# Raspi_Photometer.net
KiCad netlist of a schematic drawn in EAGLE
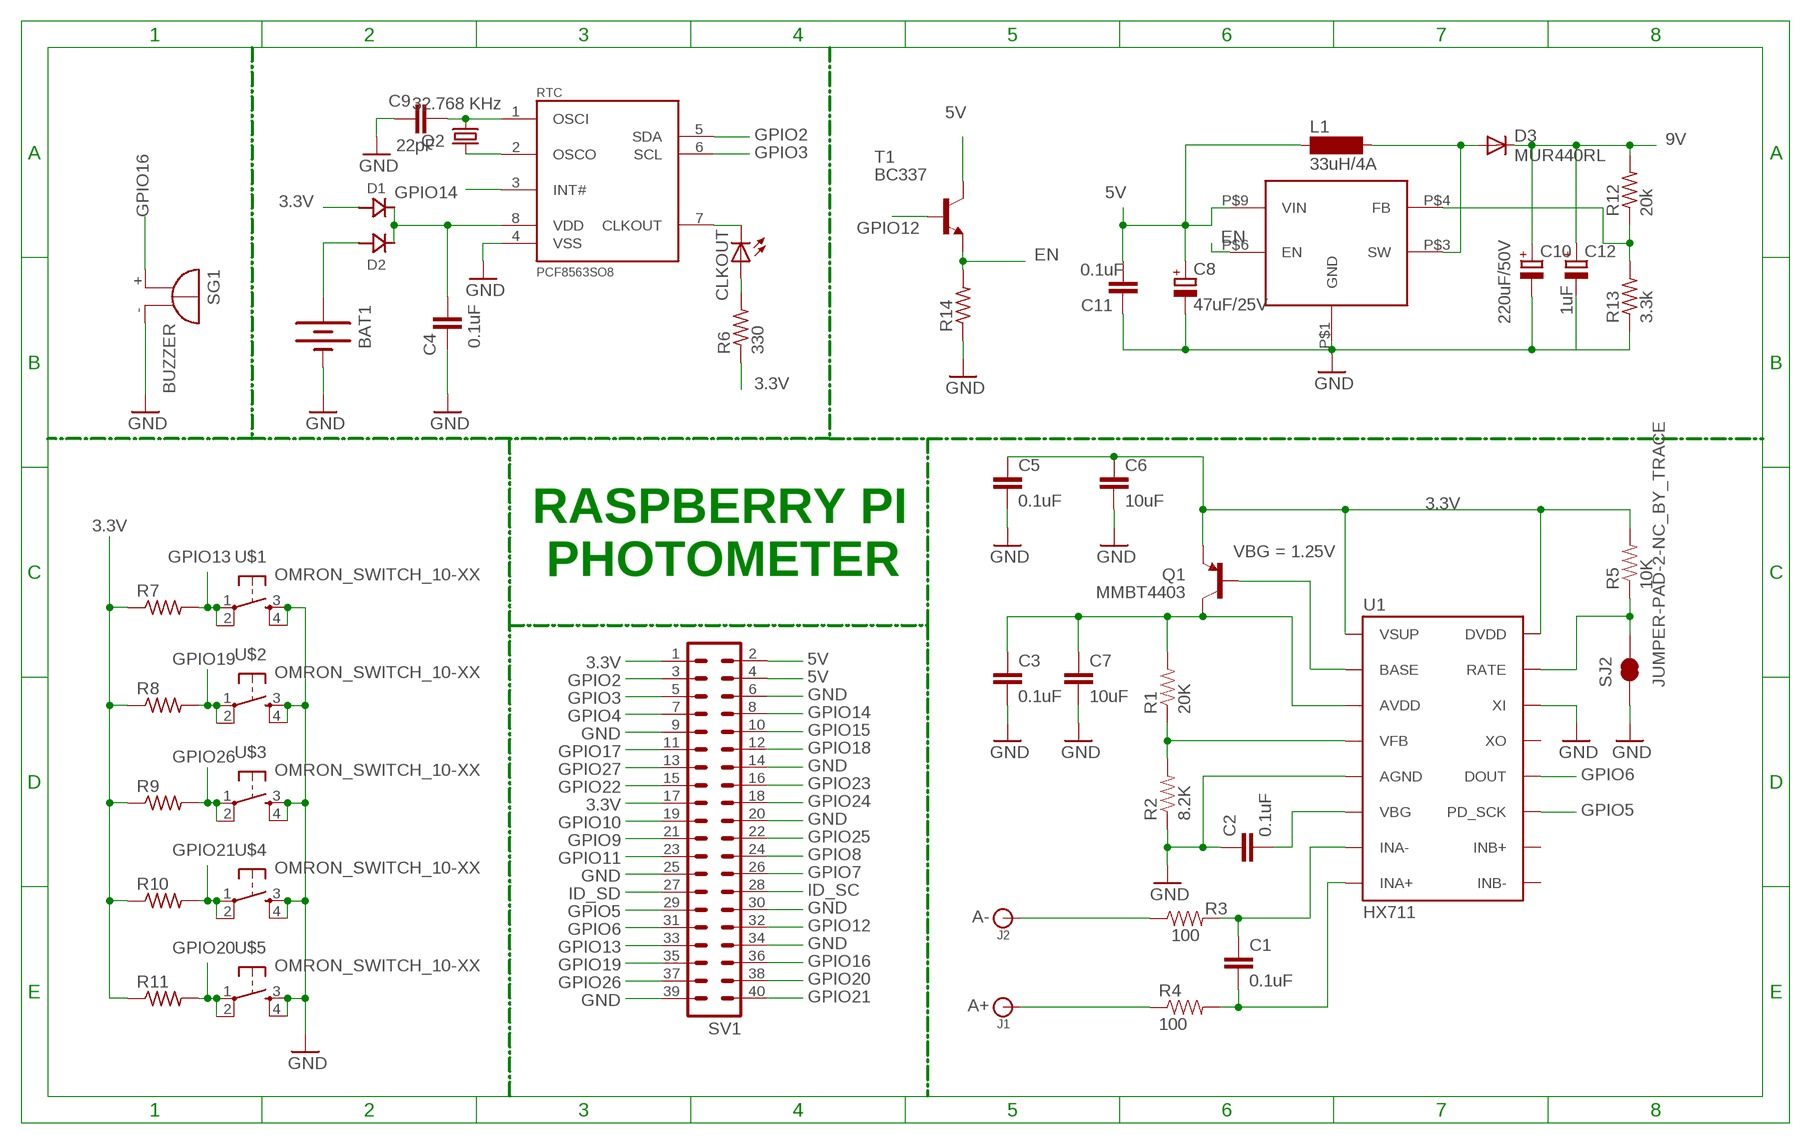
[diagram p0: schematic, sheet 1]

(export (version "E")
  (design (tool "Eeschema 10.0.6"))
  (components
    (comp (ref "BAT1")
      (value "BATTERY20PTH")
      (footprint "eagle-import:BATTCOM_20MM_PTH")
      (libsource (lib "eagle-import") (part "BATTERY20PTH"))
    )
    (comp (ref "C1")
      (value "0.1uF")
      (footprint "eagle-import:0603-CAP")
      (libsource (lib "eagle-import") (part "0.1UF-25V-5%(0603)"))
    )
    (comp (ref "C2")
      (value "0.1uF")
      (footprint "eagle-import:0603-CAP")
      (libsource (lib "eagle-import") (part "0.1UF-25V-5%(0603)"))
    )
    (comp (ref "C3")
      (value "0.1uF")
      (footprint "eagle-import:0603-CAP")
      (libsource (lib "eagle-import") (part "0.1UF-25V-5%(0603)"))
    )
    (comp (ref "C4")
      (value "0.1uF")
      (footprint "eagle-import:C0805K")
      (libsource (lib "eagle-import") (part "C-EUC0805K"))
    )
    (comp (ref "C5")
      (value "0.1uF")
      (footprint "eagle-import:0603-CAP")
      (libsource (lib "eagle-import") (part "0.1UF-25V-5%(0603)"))
    )
    (comp (ref "C6")
      (value "10uF")
      (footprint "eagle-import:1210")
      (libsource (lib "eagle-import") (part "10UF50V20%(1210)"))
    )
    (comp (ref "C7")
      (value "10uF")
      (footprint "eagle-import:1210")
      (libsource (lib "eagle-import") (part "10UF50V20%(1210)"))
    )
    (comp (ref "C8")
      (value "47uF/25V")
      (footprint "eagle-import:E3,5-10")
      (libsource (lib "eagle-import") (part "CPOL-EUE3.5-10"))
    )
    (comp (ref "C9")
      (value "22pF")
      (footprint "eagle-import:C0805K")
      (libsource (lib "eagle-import") (part "C-EUC0805K"))
    )
    (comp (ref "C10")
      (value "220uF/50V")
      (footprint "eagle-import:E5-10,5")
      (libsource (lib "eagle-import") (part "CPOL-EUE5-10.5"))
    )
    (comp (ref "C11")
      (value "0.1uF")
      (footprint "eagle-import:C0603")
      (libsource (lib "eagle-import") (part "C-EUC0603"))
    )
    (comp (ref "C12")
      (value "1uF")
      (footprint "eagle-import:E2,5-5")
      (libsource (lib "eagle-import") (part "rcl (2)_CPOL-EUE2.5-5"))
    )
    (comp (ref "CLKOUT")
      (value "LED0805")
      (footprint "eagle-import:CHIPLED_0805")
      (libsource (lib "eagle-import") (part "LED0805"))
    )
    (comp (ref "D1")
      (value "SS14")
      (footprint "eagle-import:DO214")
      (libsource (lib "eagle-import") (part "SS14"))
    )
    (comp (ref "D2")
      (value "SS14")
      (footprint "eagle-import:DO214")
      (libsource (lib "eagle-import") (part "SS14"))
    )
    (comp (ref "D3")
      (value "MUR440RL")
      (footprint "eagle-import:C2673")
      (libsource (lib "eagle-import") (part "MUR440RL"))
    )
    (comp (ref "J1")
      (value "BANANA_CONN")
      (footprint "eagle-import:BANANA_CONN")
      (libsource (lib "eagle-import") (part "BANANA_CONN"))
    )
    (comp (ref "J2")
      (value "BANANA_CONN")
      (footprint "eagle-import:BANANA_CONN")
      (libsource (lib "eagle-import") (part "BANANA_CONN"))
    )
    (comp (ref "L1")
      (value "33uH/4A")
      (footprint "eagle-import:MS85")
      (libsource (lib "eagle-import") (part "MS85"))
    )
    (comp (ref "Q1")
      (value "MMBT4403")
      (footprint "eagle-import:SOT23-3")
      (libsource (lib "eagle-import") (part "TRANSISTOR_PNPMMBT4403"))
    )
    (comp (ref "Q2")
      (value "32.768 KHz")
      (footprint "eagle-import:TC26H")
      (libsource (lib "eagle-import") (part "CRYSTALTC26H"))
    )
    (comp (ref "R1")
      (value "20K")
      (footprint "eagle-import:0603-RES")
      (libsource (lib "eagle-import") (part "20KOHM1/10W1%(0603)"))
    )
    (comp (ref "R2")
      (value "8.2K")
      (footprint "eagle-import:0603-RES")
      (libsource (lib "eagle-import") (part "8.2KOHM-1/10W-5%(0603)"))
    )
    (comp (ref "R3")
      (value "100")
      (footprint "eagle-import:0603-RES")
      (libsource (lib "eagle-import") (part "100OHM-1/10W-1%(0603)"))
    )
    (comp (ref "R4")
      (value "100")
      (footprint "eagle-import:0603-RES")
      (libsource (lib "eagle-import") (part "100OHM-1/10W-1%(0603)"))
    )
    (comp (ref "R5")
      (value "10K")
      (footprint "eagle-import:0603-RES")
      (libsource (lib "eagle-import") (part "10KOHM-1/10W-1%(0603)0603"))
    )
    (comp (ref "R6")
      (value "330")
      (footprint "eagle-import:0204_7")
      (libsource (lib "eagle-import") (part "R-US_0204/7"))
    )
    (comp (ref "R7")
      (value "R-US_0204/7")
      (footprint "eagle-import:0204_7")
      (libsource (lib "eagle-import") (part "R-US_0204/7"))
    )
    (comp (ref "R8")
      (value "R-US_0204/7")
      (footprint "eagle-import:0204_7")
      (libsource (lib "eagle-import") (part "R-US_0204/7"))
    )
    (comp (ref "R9")
      (value "R-US_0204/7")
      (footprint "eagle-import:0204_7")
      (libsource (lib "eagle-import") (part "R-US_0204/7"))
    )
    (comp (ref "R10")
      (value "R-US_0204/7")
      (footprint "eagle-import:0204_7")
      (libsource (lib "eagle-import") (part "R-US_0204/7"))
    )
    (comp (ref "R11")
      (value "R-US_0204/7")
      (footprint "eagle-import:0204_7")
      (libsource (lib "eagle-import") (part "R-US_0204/7"))
    )
    (comp (ref "R12")
      (value "20k")
      (footprint "eagle-import:0207_7")
      (libsource (lib "eagle-import") (part "RESISTOR0207/7"))
    )
    (comp (ref "R13")
      (value "3.3k")
      (footprint "eagle-import:0207_7")
      (libsource (lib "eagle-import") (part "RESISTOR0207/7"))
    )
    (comp (ref "R14")
      (value "R-US_0207/10")
      (footprint "eagle-import:0207_10")
      (libsource (lib "eagle-import") (part "R-US_0207/10"))
    )
    (comp (ref "RTC")
      (value "PCF8563SO8")
      (footprint "eagle-import:SOIC8")
      (libsource (lib "eagle-import") (part "PCF8563SO8"))
    )
    (comp (ref "SG1")
      (value "BUZZER")
      (footprint "eagle-import:F_TMB")
      (libsource (lib "eagle-import") (part "BUZZER"))
    )
    (comp (ref "SJ2")
      (value "JUMPER-PAD-2-NC_BY_TRACE")
      (footprint "eagle-import:PAD-JUMPER-2-NC_BY_TRACE_YES_SILK")
      (libsource (lib "eagle-import") (part "JUMPER-PAD-2-NC_BY_TRACE"))
    )
    (comp (ref "SV1")
      (value "ML40")
      (footprint "eagle-import:ML40")
      (libsource (lib "eagle-import") (part "ML40"))
    )
    (comp (ref "T1")
      (value "BC337")
      (footprint "eagle-import:TO92")
      (libsource (lib "eagle-import") (part "BC337"))
    )
    (comp (ref "U$1")
      (value "OMRON_SWITCH_10-XX")
      (footprint "eagle-import:B3F-10XX")
      (libsource (lib "eagle-import") (part "OMRON_SWITCH_10-XX"))
    )
    (comp (ref "U$2")
      (value "OMRON_SWITCH_10-XX")
      (footprint "eagle-import:B3F-10XX")
      (libsource (lib "eagle-import") (part "OMRON_SWITCH_10-XX"))
    )
    (comp (ref "U$3")
      (value "OMRON_SWITCH_10-XX")
      (footprint "eagle-import:B3F-10XX")
      (libsource (lib "eagle-import") (part "OMRON_SWITCH_10-XX"))
    )
    (comp (ref "U$4")
      (value "OMRON_SWITCH_10-XX")
      (footprint "eagle-import:B3F-10XX")
      (libsource (lib "eagle-import") (part "OMRON_SWITCH_10-XX"))
    )
    (comp (ref "U$5")
      (value "OMRON_SWITCH_10-XX")
      (footprint "eagle-import:B3F-10XX")
      (libsource (lib "eagle-import") (part "OMRON_SWITCH_10-XX"))
    )
    (comp (ref "U$6")
      (value "XL6009")
      (footprint "eagle-import:TO-263-5L")
      (libsource (lib "eagle-import") (part "XL6009"))
    )
    (comp (ref "U1")
      (value "HX711")
      (footprint "eagle-import:SO16")
      (libsource (lib "eagle-import") (part "HX711HX711"))
    )
  )
  (nets
    (net (code "1") (name "/3.3V") (class "Default")
      (node (ref "C5") (pin "1") (pinfunction "1_1") (pintype "passive"))
      (node (ref "C6") (pin "1") (pinfunction "1_1") (pintype "passive"))
      (node (ref "D1") (pin "ANODE") (pinfunction "ANODE_ANODE") (pintype "bidirectional"))
      (node (ref "Q1") (pin "2") (pinfunction "E_2") (pintype "passive"))
      (node (ref "R10") (pin "1") (pinfunction "1_1") (pintype "passive"))
      (node (ref "R11") (pin "1") (pinfunction "1_1") (pintype "passive"))
      (node (ref "R5") (pin "2") (pinfunction "2_2") (pintype "passive"))
      (node (ref "R6") (pin "1") (pinfunction "1_1") (pintype "passive"))
      (node (ref "R7") (pin "1") (pinfunction "1_1") (pintype "passive"))
      (node (ref "R8") (pin "1") (pinfunction "1_1") (pintype "passive"))
      (node (ref "R9") (pin "1") (pinfunction "1_1") (pintype "passive"))
      (node (ref "SV1") (pin "1") (pinfunction "1_1") (pintype "passive"))
      (node (ref "SV1") (pin "17") (pinfunction "17_17") (pintype "passive"))
      (node (ref "U1") (pin "1") (pinfunction "VSUP_1") (pintype "bidirectional"))
      (node (ref "U1") (pin "16") (pinfunction "DVDD_16") (pintype "bidirectional"))
    )
    (net (code "2") (name "/5V") (class "Default")
      (node (ref "C11") (pin "2") (pinfunction "2_2") (pintype "passive"))
      (node (ref "C8") (pin "+") (pinfunction "+_+") (pintype "passive"))
      (node (ref "L1") (pin "1") (pinfunction "1_1") (pintype "passive"))
      (node (ref "SV1") (pin "2") (pinfunction "2_2") (pintype "passive"))
      (node (ref "SV1") (pin "4") (pinfunction "4_4") (pintype "passive"))
      (node (ref "T1") (pin "3") (pinfunction "C_3") (pintype "passive"))
      (node (ref "U$6") (pin "P$9") (pinfunction "VIN_P$9") (pintype "bidirectional"))
    )
    (net (code "3") (name "/9V") (class "Default")
      (node (ref "C10") (pin "+") (pinfunction "+_+") (pintype "passive"))
      (node (ref "C12") (pin "+") (pinfunction "+_+") (pintype "passive"))
      (node (ref "D3") (pin "C") (pinfunction "C_C") (pintype "passive"))
      (node (ref "R12") (pin "2") (pinfunction "2_2") (pintype "passive"))
    )
    (net (code "4") (name "/A+") (class "Default")
      (node (ref "J1") (pin "P$2") (pinfunction "1_P$2") (pintype "passive"))
      (node (ref "R4") (pin "1") (pinfunction "1_1") (pintype "passive"))
    )
    (net (code "5") (name "/A-") (class "Default")
      (node (ref "J2") (pin "P$2") (pinfunction "1_P$2") (pintype "passive"))
      (node (ref "R3") (pin "1") (pinfunction "1_1") (pintype "passive"))
    )
    (net (code "6") (name "/EN") (class "Default")
      (node (ref "R14") (pin "2") (pinfunction "2_2") (pintype "passive"))
      (node (ref "T1") (pin "1") (pinfunction "E_1") (pintype "passive"))
      (node (ref "U$6") (pin "P$6") (pinfunction "EN_P$6") (pintype "bidirectional"))
    )
    (net (code "7") (name "/GPIO2") (class "Default")
      (node (ref "RTC") (pin "5") (pinfunction "SDA_5") (pintype "bidirectional"))
      (node (ref "SV1") (pin "3") (pinfunction "3_3") (pintype "passive"))
    )
    (net (code "8") (name "/GPIO3") (class "Default")
      (node (ref "RTC") (pin "6") (pinfunction "SCL_6") (pintype "bidirectional"))
      (node (ref "SV1") (pin "5") (pinfunction "5_5") (pintype "passive"))
    )
    (net (code "9") (name "/GPIO4") (class "Default")
      (node (ref "SV1") (pin "7") (pinfunction "7_7") (pintype "passive"))
    )
    (net (code "10") (name "/GPIO5") (class "Default")
      (node (ref "SV1") (pin "29") (pinfunction "29_29") (pintype "passive"))
      (node (ref "U1") (pin "11") (pinfunction "PD_SCK_11") (pintype "bidirectional"))
    )
    (net (code "11") (name "/GPIO6") (class "Default")
      (node (ref "SV1") (pin "31") (pinfunction "31_31") (pintype "passive"))
      (node (ref "U1") (pin "12") (pinfunction "DOUT_12") (pintype "bidirectional"))
    )
    (net (code "12") (name "/GPIO7") (class "Default")
      (node (ref "SV1") (pin "26") (pinfunction "26_26") (pintype "passive"))
    )
    (net (code "13") (name "/GPIO8") (class "Default")
      (node (ref "SV1") (pin "24") (pinfunction "24_24") (pintype "passive"))
    )
    (net (code "14") (name "/GPIO9") (class "Default")
      (node (ref "SV1") (pin "21") (pinfunction "21_21") (pintype "passive"))
    )
    (net (code "15") (name "/GPIO10") (class "Default")
      (node (ref "SV1") (pin "19") (pinfunction "19_19") (pintype "passive"))
    )
    (net (code "16") (name "/GPIO11") (class "Default")
      (node (ref "SV1") (pin "23") (pinfunction "23_23") (pintype "passive"))
    )
    (net (code "17") (name "/GPIO12") (class "Default")
      (node (ref "SV1") (pin "32") (pinfunction "32_32") (pintype "passive"))
      (node (ref "T1") (pin "2") (pinfunction "B_2") (pintype "passive"))
    )
    (net (code "18") (name "/GPIO13") (class "Default")
      (node (ref "R7") (pin "2") (pinfunction "2_2") (pintype "passive"))
      (node (ref "SV1") (pin "33") (pinfunction "33_33") (pintype "passive"))
      (node (ref "U$1") (pin "1") (pinfunction "P_1") (pintype "passive"))
      (node (ref "U$1") (pin "2") (pinfunction "P1_2") (pintype "passive"))
    )
    (net (code "19") (name "/GPIO14") (class "Default")
      (node (ref "RTC") (pin "3") (pinfunction "INT#_3") (pintype "bidirectional"))
      (node (ref "SV1") (pin "8") (pinfunction "8_8") (pintype "passive"))
    )
    (net (code "20") (name "/GPIO15") (class "Default")
      (node (ref "SV1") (pin "10") (pinfunction "10_10") (pintype "passive"))
    )
    (net (code "21") (name "/GPIO16") (class "Default")
      (node (ref "SG1") (pin "+") (pinfunction "+_+") (pintype "passive"))
      (node (ref "SV1") (pin "36") (pinfunction "36_36") (pintype "passive"))
    )
    (net (code "22") (name "/GPIO17") (class "Default")
      (node (ref "SV1") (pin "11") (pinfunction "11_11") (pintype "passive"))
    )
    (net (code "23") (name "/GPIO18") (class "Default")
      (node (ref "SV1") (pin "12") (pinfunction "12_12") (pintype "passive"))
    )
    (net (code "24") (name "/GPIO19") (class "Default")
      (node (ref "R8") (pin "2") (pinfunction "2_2") (pintype "passive"))
      (node (ref "SV1") (pin "35") (pinfunction "35_35") (pintype "passive"))
      (node (ref "U$2") (pin "1") (pinfunction "P_1") (pintype "passive"))
      (node (ref "U$2") (pin "2") (pinfunction "P1_2") (pintype "passive"))
    )
    (net (code "25") (name "/GPIO20") (class "Default")
      (node (ref "R11") (pin "2") (pinfunction "2_2") (pintype "passive"))
      (node (ref "SV1") (pin "38") (pinfunction "38_38") (pintype "passive"))
      (node (ref "U$5") (pin "1") (pinfunction "P_1") (pintype "passive"))
      (node (ref "U$5") (pin "2") (pinfunction "P1_2") (pintype "passive"))
    )
    (net (code "26") (name "/GPIO21") (class "Default")
      (node (ref "R10") (pin "2") (pinfunction "2_2") (pintype "passive"))
      (node (ref "SV1") (pin "40") (pinfunction "40_40") (pintype "passive"))
      (node (ref "U$4") (pin "1") (pinfunction "P_1") (pintype "passive"))
      (node (ref "U$4") (pin "2") (pinfunction "P1_2") (pintype "passive"))
    )
    (net (code "27") (name "/GPIO22") (class "Default")
      (node (ref "SV1") (pin "15") (pinfunction "15_15") (pintype "passive"))
    )
    (net (code "28") (name "/GPIO23") (class "Default")
      (node (ref "SV1") (pin "16") (pinfunction "16_16") (pintype "passive"))
    )
    (net (code "29") (name "/GPIO24") (class "Default")
      (node (ref "SV1") (pin "18") (pinfunction "18_18") (pintype "passive"))
    )
    (net (code "30") (name "/GPIO25") (class "Default")
      (node (ref "SV1") (pin "22") (pinfunction "22_22") (pintype "passive"))
    )
    (net (code "31") (name "/GPIO26") (class "Default")
      (node (ref "R9") (pin "2") (pinfunction "2_2") (pintype "passive"))
      (node (ref "SV1") (pin "37") (pinfunction "37_37") (pintype "passive"))
      (node (ref "U$3") (pin "1") (pinfunction "P_1") (pintype "passive"))
      (node (ref "U$3") (pin "2") (pinfunction "P1_2") (pintype "passive"))
    )
    (net (code "32") (name "/GPIO27") (class "Default")
      (node (ref "SV1") (pin "13") (pinfunction "13_13") (pintype "passive"))
    )
    (net (code "33") (name "/ID_SC") (class "Default")
      (node (ref "SV1") (pin "28") (pinfunction "28_28") (pintype "passive"))
    )
    (net (code "34") (name "/ID_SD") (class "Default")
      (node (ref "SV1") (pin "27") (pinfunction "27_27") (pintype "passive"))
    )
    (net (code "35") (name "GND") (class "Default")
      (node (ref "BAT1") (pin "2") (pinfunction "-_2") (pintype "power_in"))
      (node (ref "C10") (pin "-") (pinfunction "-_-") (pintype "passive"))
      (node (ref "C11") (pin "1") (pinfunction "1_1") (pintype "passive"))
      (node (ref "C12") (pin "-") (pinfunction "-_-") (pintype "passive"))
      (node (ref "C2") (pin "1") (pinfunction "1_1") (pintype "passive"))
      (node (ref "C3") (pin "2") (pinfunction "2_2") (pintype "passive"))
      (node (ref "C4") (pin "1") (pinfunction "1_1") (pintype "passive"))
      (node (ref "C5") (pin "2") (pinfunction "2_2") (pintype "passive"))
      (node (ref "C6") (pin "2") (pinfunction "2_2") (pintype "passive"))
      (node (ref "C7") (pin "2") (pinfunction "2_2") (pintype "passive"))
      (node (ref "C8") (pin "-") (pinfunction "-_-") (pintype "passive"))
      (node (ref "C9") (pin "1") (pinfunction "1_1") (pintype "passive"))
      (node (ref "R13") (pin "1") (pinfunction "1_1") (pintype "passive"))
      (node (ref "R14") (pin "1") (pinfunction "1_1") (pintype "passive"))
      (node (ref "R2") (pin "1") (pinfunction "1_1") (pintype "passive"))
      (node (ref "RTC") (pin "4") (pinfunction "VSS_4") (pintype "bidirectional"))
      (node (ref "SG1") (pin "-") (pinfunction "-_-") (pintype "passive"))
      (node (ref "SJ2") (pin "1") (pinfunction "1_1") (pintype "passive"))
      (node (ref "SV1") (pin "14") (pinfunction "14_14") (pintype "passive"))
      (node (ref "SV1") (pin "20") (pinfunction "20_20") (pintype "passive"))
      (node (ref "SV1") (pin "25") (pinfunction "25_25") (pintype "passive"))
      (node (ref "SV1") (pin "30") (pinfunction "30_30") (pintype "passive"))
      (node (ref "SV1") (pin "34") (pinfunction "34_34") (pintype "passive"))
      (node (ref "SV1") (pin "39") (pinfunction "39_39") (pintype "passive"))
      (node (ref "SV1") (pin "6") (pinfunction "6_6") (pintype "passive"))
      (node (ref "SV1") (pin "9") (pinfunction "9_9") (pintype "passive"))
      (node (ref "U$1") (pin "3") (pinfunction "S_3") (pintype "passive"))
      (node (ref "U$1") (pin "4") (pinfunction "S1_4") (pintype "passive"))
      (node (ref "U$2") (pin "3") (pinfunction "S_3") (pintype "passive"))
      (node (ref "U$2") (pin "4") (pinfunction "S1_4") (pintype "passive"))
      (node (ref "U$3") (pin "3") (pinfunction "S_3") (pintype "passive"))
      (node (ref "U$3") (pin "4") (pinfunction "S1_4") (pintype "passive"))
      (node (ref "U$4") (pin "3") (pinfunction "S_3") (pintype "passive"))
      (node (ref "U$4") (pin "4") (pinfunction "S1_4") (pintype "passive"))
      (node (ref "U$5") (pin "3") (pinfunction "S_3") (pintype "passive"))
      (node (ref "U$5") (pin "4") (pinfunction "S1_4") (pintype "passive"))
      (node (ref "U$6") (pin "P$1") (pinfunction "GND_P$1") (pintype "bidirectional"))
      (node (ref "U1") (pin "14") (pinfunction "XI_14") (pintype "bidirectional"))
      (node (ref "U1") (pin "5") (pinfunction "AGND_5") (pintype "bidirectional"))
    )
    (net (code "36") (name "Net-(BAT1-+)") (class "Default")
      (node (ref "BAT1") (pin "1") (pinfunction "+_1") (pintype "power_in"))
      (node (ref "D2") (pin "ANODE") (pinfunction "ANODE_ANODE") (pintype "bidirectional"))
    )
    (net (code "37") (name "Net-(CLKOUT-PadA)") (class "Default")
      (node (ref "CLKOUT") (pin "A") (pinfunction "A_A") (pintype "passive"))
      (node (ref "R6") (pin "2") (pinfunction "2_2") (pintype "passive"))
    )
    (net (code "38") (name "Net-(Q1-B)") (class "Default")
      (node (ref "Q1") (pin "1") (pinfunction "B_1") (pintype "passive"))
      (node (ref "U1") (pin "2") (pinfunction "BASE_2") (pintype "bidirectional"))
    )
    (net (code "39") (name "Net-(Q1-C)") (class "Default")
      (node (ref "C3") (pin "1") (pinfunction "1_1") (pintype "passive"))
      (node (ref "C7") (pin "1") (pinfunction "1_1") (pintype "passive"))
      (node (ref "Q1") (pin "3") (pinfunction "C_3") (pintype "passive"))
      (node (ref "R1") (pin "2") (pinfunction "2_2") (pintype "passive"))
      (node (ref "U1") (pin "3") (pinfunction "AVDD_3") (pintype "bidirectional"))
    )
    (net (code "40") (name "Net-(RTC-CLKOUT)") (class "Default")
      (node (ref "CLKOUT") (pin "C") (pinfunction "C_C") (pintype "passive"))
      (node (ref "RTC") (pin "7") (pinfunction "CLKOUT_7") (pintype "bidirectional"))
    )
    (net (code "41") (name "Net-(RTC-OSCI)") (class "Default")
      (node (ref "C9") (pin "2") (pinfunction "2_2") (pintype "passive"))
      (node (ref "Q2") (pin "1") (pinfunction "1_1") (pintype "passive"))
      (node (ref "RTC") (pin "1") (pinfunction "OSCI_1") (pintype "bidirectional"))
    )
    (net (code "42") (name "Net-(RTC-OSCO)") (class "Default")
      (node (ref "Q2") (pin "2") (pinfunction "2_2") (pintype "passive"))
      (node (ref "RTC") (pin "2") (pinfunction "OSCO_2") (pintype "bidirectional"))
    )
    (net (code "43") (name "Net-(RTC-VDD)") (class "Default")
      (node (ref "C4") (pin "2") (pinfunction "2_2") (pintype "passive"))
      (node (ref "D1") (pin "CATHODE") (pinfunction "CATHODE_CATHODE") (pintype "bidirectional"))
      (node (ref "D2") (pin "CATHODE") (pinfunction "CATHODE_CATHODE") (pintype "bidirectional"))
      (node (ref "RTC") (pin "8") (pinfunction "VDD_8") (pintype "bidirectional"))
    )
    (net (code "44") (name "Net-(U$6-FB)") (class "Default")
      (node (ref "R12") (pin "1") (pinfunction "1_1") (pintype "passive"))
      (node (ref "R13") (pin "2") (pinfunction "2_2") (pintype "passive"))
      (node (ref "U$6") (pin "P$4") (pinfunction "FB_P$4") (pintype "bidirectional"))
    )
    (net (code "45") (name "Net-(U$6-SW)") (class "Default")
      (node (ref "D3") (pin "A") (pinfunction "A_A") (pintype "passive"))
      (node (ref "L1") (pin "2") (pinfunction "2_2") (pintype "passive"))
      (node (ref "U$6") (pin "P$3") (pinfunction "SW_P$3") (pintype "bidirectional"))
    )
    (net (code "46") (name "Net-(U1-INA+)") (class "Default")
      (node (ref "C1") (pin "2") (pinfunction "2_2") (pintype "passive"))
      (node (ref "R4") (pin "2") (pinfunction "2_2") (pintype "passive"))
      (node (ref "U1") (pin "8") (pinfunction "INA+_8") (pintype "bidirectional"))
    )
    (net (code "47") (name "Net-(U1-INA-)") (class "Default")
      (node (ref "C1") (pin "1") (pinfunction "1_1") (pintype "passive"))
      (node (ref "R3") (pin "2") (pinfunction "2_2") (pintype "passive"))
      (node (ref "U1") (pin "7") (pinfunction "INA-_7") (pintype "bidirectional"))
    )
    (net (code "48") (name "Net-(U1-RATE)") (class "Default")
      (node (ref "R5") (pin "1") (pinfunction "1_1") (pintype "passive"))
      (node (ref "SJ2") (pin "2") (pinfunction "2_2") (pintype "passive"))
      (node (ref "U1") (pin "15") (pinfunction "RATE_15") (pintype "bidirectional"))
    )
    (net (code "49") (name "Net-(U1-VBG)") (class "Default")
      (node (ref "C2") (pin "2") (pinfunction "2_2") (pintype "passive"))
      (node (ref "U1") (pin "6") (pinfunction "VBG_6") (pintype "bidirectional"))
    )
    (net (code "50") (name "Net-(U1-VFB)") (class "Default")
      (node (ref "R1") (pin "1") (pinfunction "1_1") (pintype "passive"))
      (node (ref "R2") (pin "2") (pinfunction "2_2") (pintype "passive"))
      (node (ref "U1") (pin "4") (pinfunction "VFB_4") (pintype "bidirectional"))
    )
    (net (code "51") (name "unconnected-(U1-INB+-Pad10)") (class "Default")
      (node (ref "U1") (pin "10") (pinfunction "INB+_10") (pintype "bidirectional"))
    )
    (net (code "52") (name "unconnected-(U1-INB--Pad9)") (class "Default")
      (node (ref "U1") (pin "9") (pinfunction "INB-_9") (pintype "bidirectional"))
    )
    (net (code "53") (name "unconnected-(U1-XO-Pad13)") (class "Default")
      (node (ref "U1") (pin "13") (pinfunction "XO_13") (pintype "bidirectional"))
    )
  )
)
